# SCH_LAMPU_LALU_LINTAS_1_JALUR.net
KiCad netlist of a schematic drawn in EasyEDA
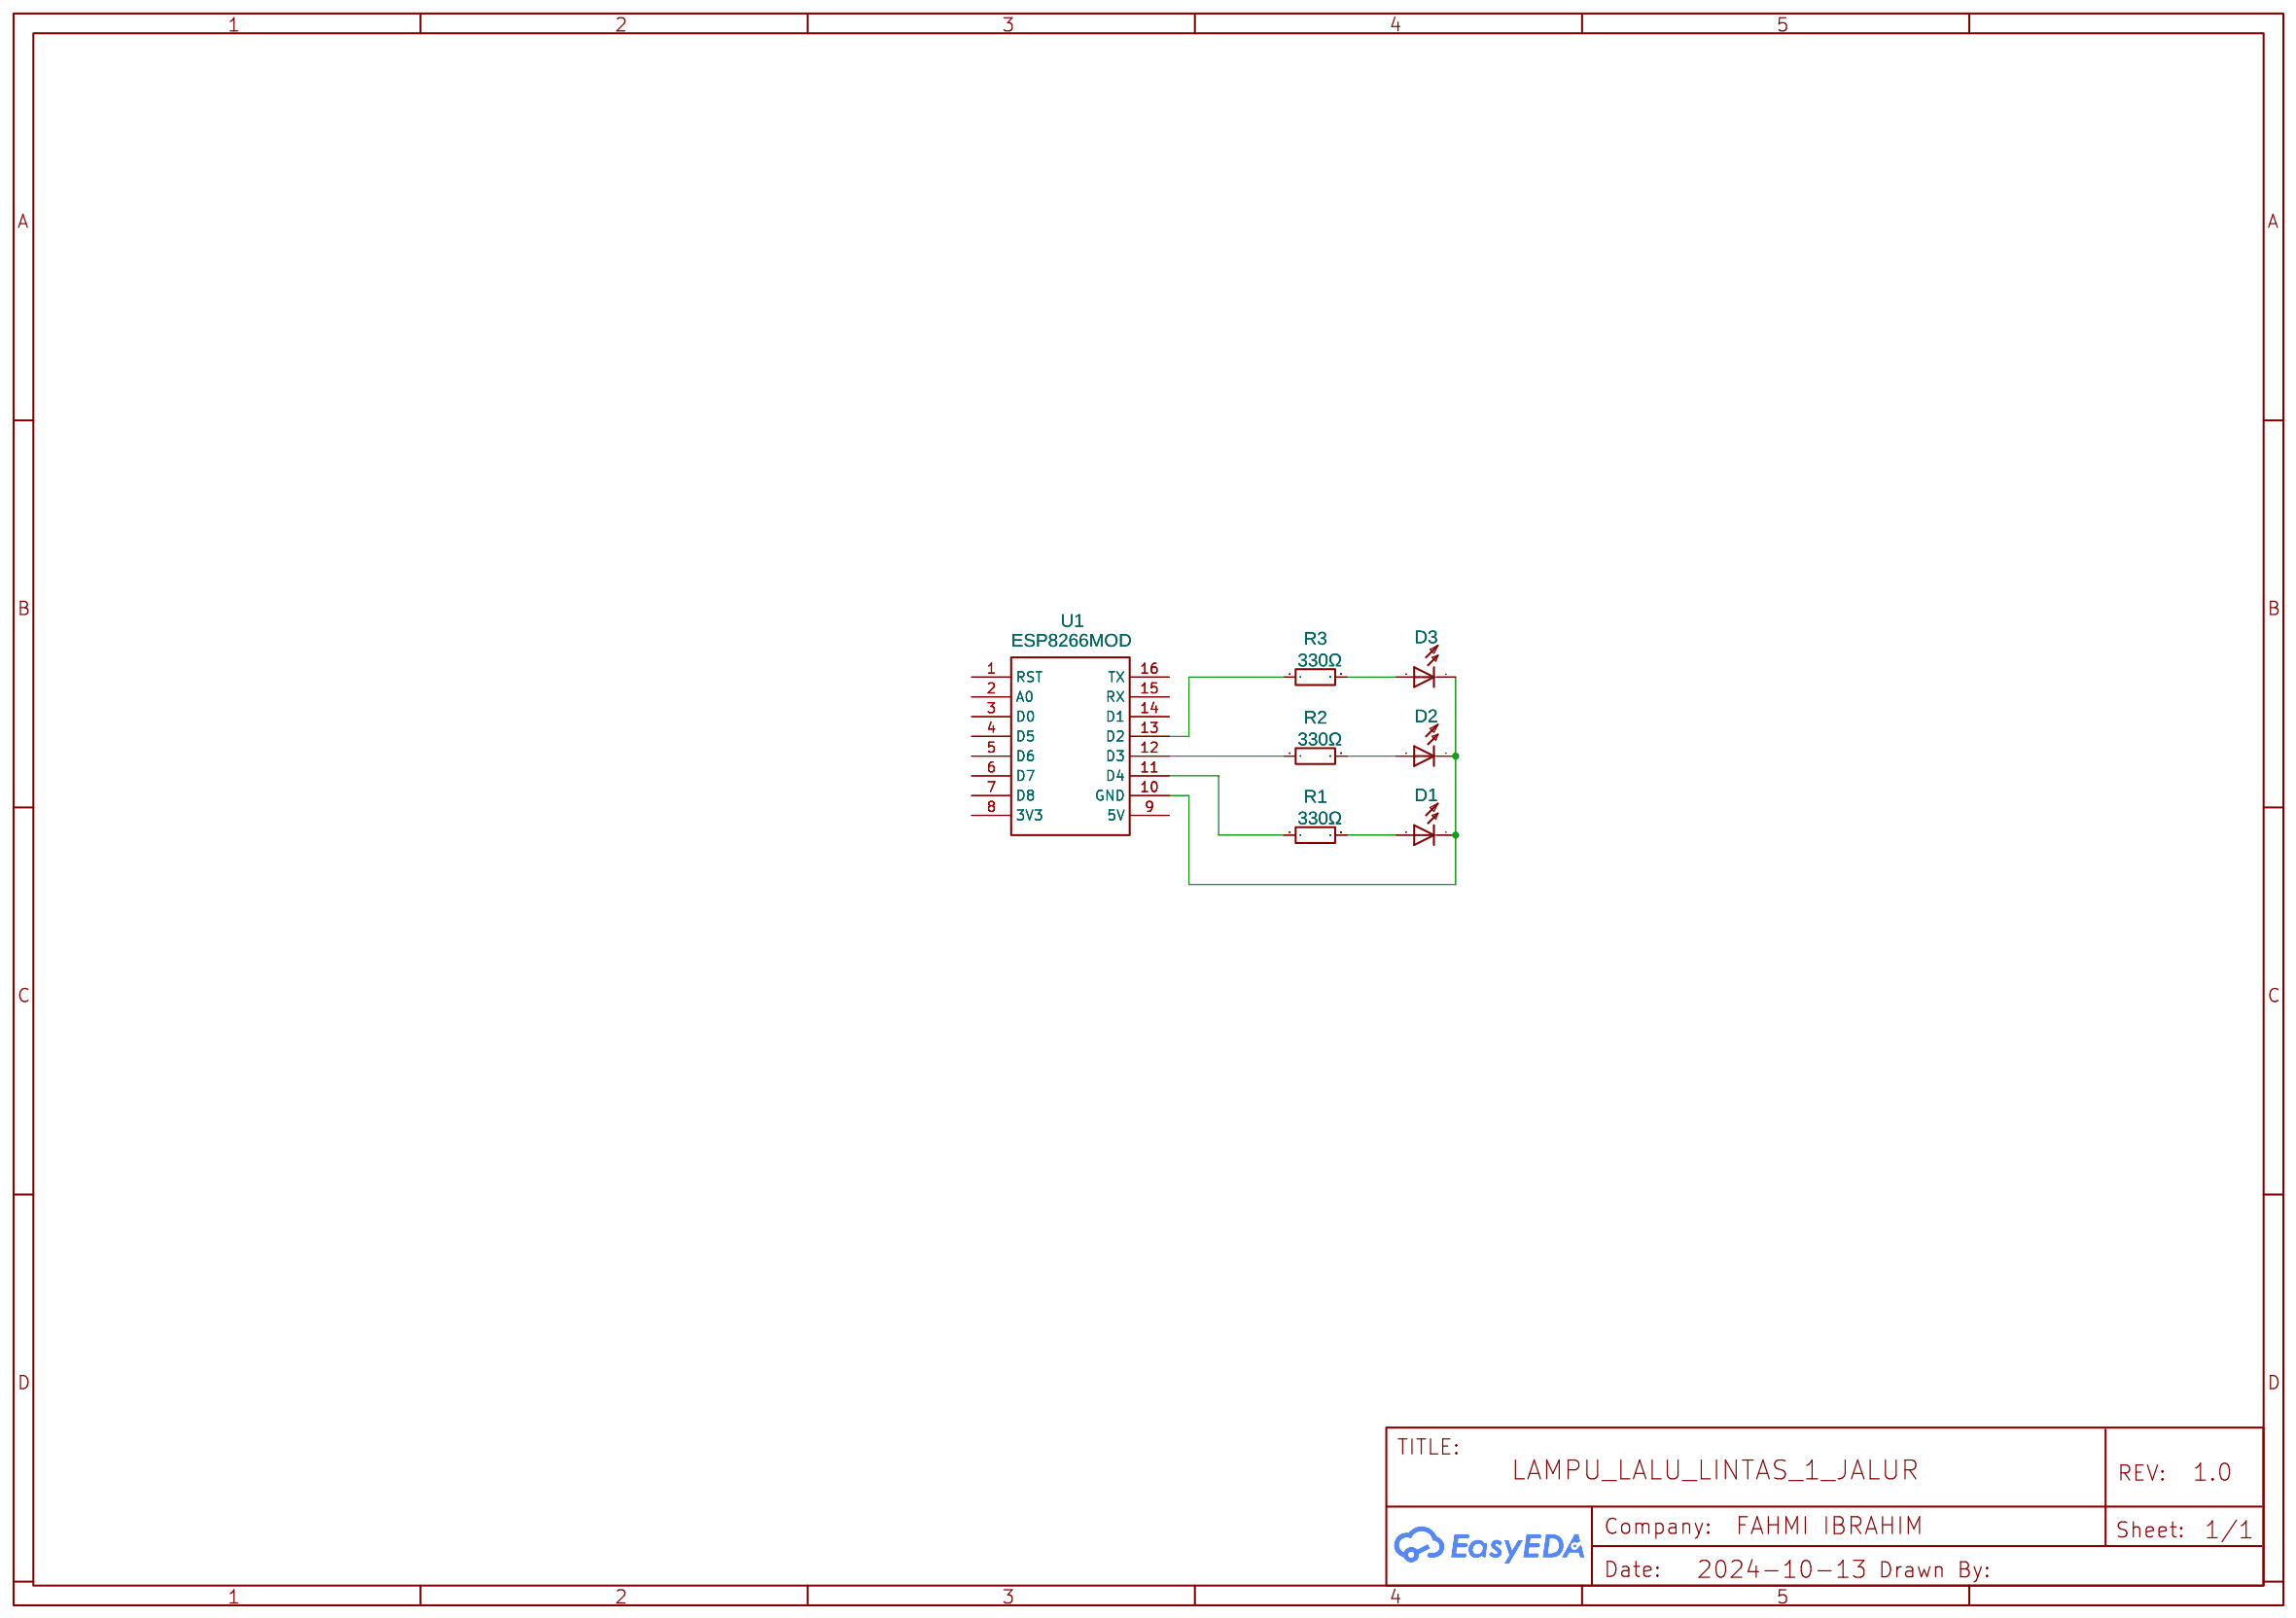
[diagram p0: schematic sheet]

(export (version "E")
  (design (tool "Eeschema 10.0.6"))
  (components
    (comp (ref "D1") (value "RED") (libsource (lib "") (part "LED 3 MM")))
    (comp (ref "D2") (value "RED") (libsource (lib "") (part "LED 3 MM")))
    (comp (ref "D3") (value "RED") (libsource (lib "") (part "LED 3 MM")))
    (comp (ref "R1")
      (value "330Ω")
      (fields
        (field (name "Manufacturer Part") "EWWR0001J20R0T9")
        (field (name "Manufacturer") "ResistorToday")
      )
      (libsource (lib "") (part "RESISTOR NORMAL"))
    )
    (comp (ref "R2")
      (value "330Ω")
      (fields
        (field (name "Manufacturer Part") "EWWR0001J20R0T9")
        (field (name "Manufacturer") "ResistorToday")
      )
      (libsource (lib "") (part "RESISTOR NORMAL"))
    )
    (comp (ref "R3")
      (value "330Ω")
      (fields
        (field (name "Manufacturer Part") "EWWR0001J20R0T9")
        (field (name "Manufacturer") "ResistorToday")
      )
      (libsource (lib "") (part "RESISTOR NORMAL"))
    )
    (comp (ref "U1") (value "ESP8266MOD") (libsource (lib "") (part "ESP8266MOD")))
  )
  (nets
    (net (code "1") (name "Net-(D1-Pad+)") (class "Default")
      (node (ref "D1") (pin "+") (pinfunction "+_+") (pintype "bidirectional"))
      (node (ref "R1") (pin "2") (pinfunction "2_2") (pintype "unspecified"))
    )
    (net (code "2") (name "Net-(D2-Pad+)") (class "Default")
      (node (ref "D2") (pin "+") (pinfunction "+_+") (pintype "bidirectional"))
      (node (ref "R2") (pin "2") (pinfunction "2_2") (pintype "unspecified"))
    )
    (net (code "3") (name "Net-(D3-Pad+)") (class "Default")
      (node (ref "D3") (pin "+") (pinfunction "+_+") (pintype "bidirectional"))
      (node (ref "R3") (pin "2") (pinfunction "2_2") (pintype "unspecified"))
    )
    (net (code "4") (name "Net-(U1-D2)") (class "Default")
      (node (ref "R3") (pin "1") (pinfunction "1_1") (pintype "unspecified"))
      (node (ref "U1") (pin "13") (pinfunction "D2_13") (pintype "unspecified"))
    )
    (net (code "5") (name "Net-(U1-D3)") (class "Default")
      (node (ref "R2") (pin "1") (pinfunction "1_1") (pintype "unspecified"))
      (node (ref "U1") (pin "12") (pinfunction "D3_12") (pintype "unspecified"))
    )
    (net (code "6") (name "Net-(U1-D4)") (class "Default")
      (node (ref "R1") (pin "1") (pinfunction "1_1") (pintype "unspecified"))
      (node (ref "U1") (pin "11") (pinfunction "D4_11") (pintype "unspecified"))
    )
    (net (code "7") (name "Net-(U1-GND)") (class "Default")
      (node (ref "D1") (pin "-") (pinfunction "-_-") (pintype "bidirectional"))
      (node (ref "D2") (pin "-") (pinfunction "-_-") (pintype "bidirectional"))
      (node (ref "D3") (pin "-") (pinfunction "-_-") (pintype "bidirectional"))
      (node (ref "U1") (pin "10") (pinfunction "GND_10") (pintype "unspecified"))
    )
    (net (code "8") (name "unconnected-(U1-3V3-Pad8)") (class "Default")
      (node (ref "U1") (pin "8") (pinfunction "3V3_8") (pintype "unspecified"))
    )
    (net (code "9") (name "unconnected-(U1-5V-Pad9)") (class "Default")
      (node (ref "U1") (pin "9") (pinfunction "5V_9") (pintype "unspecified"))
    )
    (net (code "10") (name "unconnected-(U1-A0-Pad2)") (class "Default")
      (node (ref "U1") (pin "2") (pinfunction "A0_2") (pintype "unspecified"))
    )
    (net (code "11") (name "unconnected-(U1-D0-Pad3)") (class "Default")
      (node (ref "U1") (pin "3") (pinfunction "D0_3") (pintype "unspecified"))
    )
    (net (code "12") (name "unconnected-(U1-D1-Pad14)") (class "Default")
      (node (ref "U1") (pin "14") (pinfunction "D1_14") (pintype "unspecified"))
    )
    (net (code "13") (name "unconnected-(U1-D5-Pad4)") (class "Default")
      (node (ref "U1") (pin "4") (pinfunction "D5_4") (pintype "unspecified"))
    )
    (net (code "14") (name "unconnected-(U1-D6-Pad5)") (class "Default")
      (node (ref "U1") (pin "5") (pinfunction "D6_5") (pintype "unspecified"))
    )
    (net (code "15") (name "unconnected-(U1-D7-Pad6)") (class "Default")
      (node (ref "U1") (pin "6") (pinfunction "D7_6") (pintype "unspecified"))
    )
    (net (code "16") (name "unconnected-(U1-D8-Pad7)") (class "Default")
      (node (ref "U1") (pin "7") (pinfunction "D8_7") (pintype "unspecified"))
    )
    (net (code "17") (name "unconnected-(U1-RST-Pad1)") (class "Default")
      (node (ref "U1") (pin "1") (pinfunction "RST_1") (pintype "unspecified"))
    )
    (net (code "18") (name "unconnected-(U1-RX-Pad15)") (class "Default")
      (node (ref "U1") (pin "15") (pinfunction "RX_15") (pintype "unspecified"))
    )
    (net (code "19") (name "unconnected-(U1-TX-Pad16)") (class "Default")
      (node (ref "U1") (pin "16") (pinfunction "TX_16") (pintype "unspecified"))
    )
  )
)
